# main.net
KiCad netlist of a schematic drawn in Altium Designer
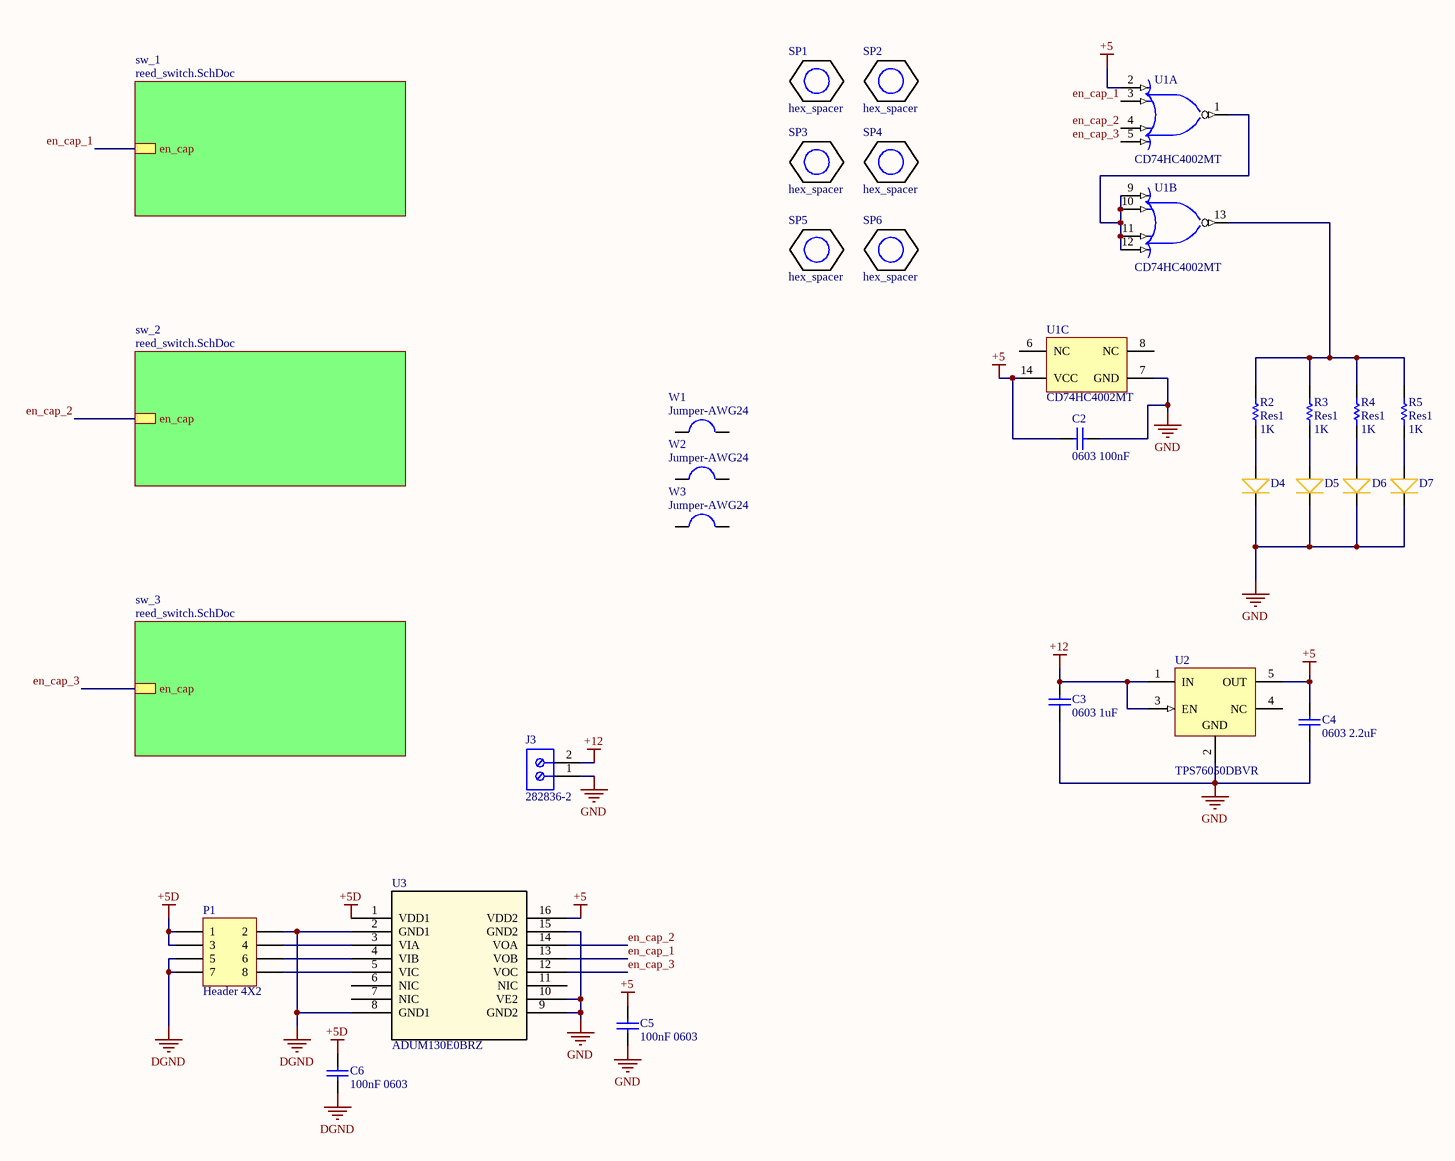
[diagram p0: main.SchDoc]

(export (version "E")
  (design (tool "Eeschema 10.0.6"))
  (components
    (comp (ref "C2")
      (value "0603 100nF")
      (footprint "CAP 0603_1608")
      (description "Capacitor")
      (fields (field (name "PUBLISHER") "Altium Limited"))
      (libsource (lib "Miscellaneous Devices") (part "Cap"))
    )
    (comp (ref "C3")
      (value "0603 1uF")
      (footprint "CAP 0603_1608")
      (description "Capacitor")
      (fields (field (name "PUBLISHER") "Altium Limited"))
      (libsource (lib "Miscellaneous Devices") (part "Cap"))
    )
    (comp (ref "C4")
      (value "0603 2.2uF")
      (footprint "CAP 0603_1608")
      (description "Capacitor")
      (fields (field (name "PUBLISHER") "Altium Limited"))
      (libsource (lib "Miscellaneous Devices") (part "Cap"))
    )
    (comp (ref "C5")
      (value "100nF 0603")
      (footprint "CAP 0603_1608")
      (description "Capacitor")
      (fields (field (name "PUBLISHER") "Altium Limited"))
      (libsource (lib "Miscellaneous Devices") (part "Cap"))
    )
    (comp (ref "C6")
      (value "100nF 0603")
      (footprint "CAP 0603_1608")
      (description "Capacitor")
      (fields (field (name "PUBLISHER") "Altium Limited"))
      (libsource (lib "Miscellaneous Devices") (part "Cap"))
    )
    (comp (ref "D4")
      (value "732-12018-1-ND")
      (footprint "LED_YELLOW_0603")
      (libsource (lib "coil_driver_lib") (part "led_yellow_0603"))
    )
    (comp (ref "D5")
      (value "732-12018-1-ND")
      (footprint "LED_YELLOW_0603")
      (libsource (lib "coil_driver_lib") (part "led_yellow_0603"))
    )
    (comp (ref "D6")
      (value "732-12018-1-ND")
      (footprint "LED_YELLOW_0603")
      (libsource (lib "coil_driver_lib") (part "led_yellow_0603"))
    )
    (comp (ref "D7")
      (value "732-12018-1-ND")
      (footprint "LED_YELLOW_0603")
      (libsource (lib "coil_driver_lib") (part "led_yellow_0603"))
    )
    (comp (ref "J3")
      (value "282836-2")
      (footprint "TECO-282836-2_V")
      (description "Female Header, Pitch 5 mm, 1 x 2 Position, Height 10 mm, Tail Length 3.5 mm, Rohs, Bulk")
      (fields (field (name "VOLTAGE") "300V") (field (name "MANUFACTURER") "TE Connectivity"))
      (libsource (lib "Altium Content Vault") (part "CN-1P-F-TB2"))
    )
    (comp (ref "P1")
      (value "Header 4X2")
      (footprint "HEADER_4_2")
      (description "Header, 4-Pin, Dual row")
      (fields (field (name "PUBLISHER") "Altium Limited"))
      (libsource (lib "Miscellaneous Connectors") (part "Header 4X2"))
    )
    (comp (ref "R2")
      (value "Res1")
      (footprint "RES 0603_1608")
      (description "Resistor")
      (fields (field (name "ALTIUM_VALUE") "1K") (field (name "PUBLISHER") "Altium Limited"))
      (libsource (lib "Miscellaneous Devices") (part "Res1"))
    )
    (comp (ref "R3")
      (value "Res1")
      (footprint "RES 0603_1608")
      (description "Resistor")
      (fields (field (name "ALTIUM_VALUE") "1K") (field (name "PUBLISHER") "Altium Limited"))
      (libsource (lib "Miscellaneous Devices") (part "Res1"))
    )
    (comp (ref "R4")
      (value "Res1")
      (footprint "RES 0603_1608")
      (description "Resistor")
      (fields (field (name "ALTIUM_VALUE") "1K") (field (name "PUBLISHER") "Altium Limited"))
      (libsource (lib "Miscellaneous Devices") (part "Res1"))
    )
    (comp (ref "R5")
      (value "Res1")
      (footprint "RES 0603_1608")
      (description "Resistor")
      (fields (field (name "ALTIUM_VALUE") "1K") (field (name "PUBLISHER") "Altium Limited"))
      (libsource (lib "Miscellaneous Devices") (part "Res1"))
    )
    (comp (ref "SP1")
      (value "hex_spacer")
      (footprint "hex_spacer")
      (libsource (lib "coil_driver_lib") (part "hex_spacer"))
    )
    (comp (ref "SP2")
      (value "hex_spacer")
      (footprint "hex_spacer")
      (libsource (lib "coil_driver_lib") (part "hex_spacer"))
    )
    (comp (ref "SP3")
      (value "hex_spacer")
      (footprint "hex_spacer")
      (libsource (lib "coil_driver_lib") (part "hex_spacer"))
    )
    (comp (ref "SP4")
      (value "hex_spacer")
      (footprint "hex_spacer")
      (libsource (lib "coil_driver_lib") (part "hex_spacer"))
    )
    (comp (ref "SP5")
      (value "hex_spacer")
      (footprint "hex_spacer")
      (libsource (lib "coil_driver_lib") (part "hex_spacer"))
    )
    (comp (ref "SP6")
      (value "hex_spacer")
      (footprint "hex_spacer")
      (libsource (lib "coil_driver_lib") (part "hex_spacer"))
    )
    (comp (ref "U1")
      (value "CD74HC4002MT")
      (footprint "D0014A_N")
      (description "High Speed CMOS Logic Dual 4-Input NOR Gates, D0014A, SMALL T&R")
      (fields
        (field (name "MANUFACTURER") "Texas Instruments")
        (field (name "GENERIC PART NUMBER") "CD74HC4002")
      )
      (libsource (lib "Altium Content Vault") (part "TI-CD_SNX4HC4002-14"))
    )
    (comp (ref "U2")
      (value "TPS76050DBVR")
      (footprint "DBV0005A_L")
      (fields (field (name "MANUFACTURER") "Texas Instruments"))
      (libsource (lib "Altium Content Vault") (part "TI-TXX7XXXX-5"))
    )
    (comp (ref "U3")
      (value "ADUM130E0BRZ")
      (footprint "R_16")
      (description "No Description Available")
      (fields (field (name "COPYRIGHT") "Copyright (C) 2021 Ultra Librarian. All rights reserved."))
      (libsource (lib "ADUM130E0BRZ") (part "ADUM130E0BRZ"))
    )
    (comp (ref "W1")
      (value "wire_jumper")
      (footprint "wire_jumper")
      (libsource (lib "coil_driver_lib") (part "wire_jumper"))
    )
    (comp (ref "W2")
      (value "wire_jumper")
      (footprint "wire_jumper")
      (libsource (lib "coil_driver_lib") (part "wire_jumper"))
    )
    (comp (ref "W3")
      (value "wire_jumper")
      (footprint "wire_jumper")
      (libsource (lib "coil_driver_lib") (part "wire_jumper"))
    )
  )
  (nets
    (net (code "1") (name "+5") (class "Default")
      (node (ref "C2") (pin "2") (pinfunction "2_2") (pintype "passive"))
      (node (ref "C4") (pin "2") (pinfunction "2_2") (pintype "passive"))
      (node (ref "C5") (pin "2") (pinfunction "2_2") (pintype "passive"))
      (node (ref "U1") (pin "14") (pinfunction "VCC_14") (pintype "power_in"))
      (node (ref "U1") (pin "2") (pinfunction "1A_2") (pintype "input"))
      (node (ref "U2") (pin "5") (pinfunction "OUT_5") (pintype "power_in"))
      (node (ref "U3") (pin "16") (pinfunction "VDD2_16") (pintype "passive"))
    )
    (net (code "2") (name "+5D") (class "Default")
      (node (ref "C6") (pin "2") (pinfunction "2_2") (pintype "passive"))
      (node (ref "P1") (pin "1") (pinfunction "1_1") (pintype "passive"))
      (node (ref "P1") (pin "3") (pinfunction "3_3") (pintype "passive"))
      (node (ref "U3") (pin "1") (pinfunction "VDD1_1") (pintype "passive"))
    )
    (net (code "3") (name "+12") (class "Default")
      (node (ref "C3") (pin "2") (pinfunction "2_2") (pintype "passive"))
      (node (ref "J3") (pin "2") (pinfunction "2_2") (pintype "passive"))
      (node (ref "U2") (pin "1") (pinfunction "IN_1") (pintype "power_in"))
      (node (ref "U2") (pin "3") (pinfunction "EN_3") (pintype "input"))
    )
    (net (code "4") (name "/en_cap_1") (class "Default")
      (node (ref "U1") (pin "3") (pinfunction "1B_3") (pintype "input"))
      (node (ref "U3") (pin "13") (pinfunction "VOB_13") (pintype "passive"))
    )
    (net (code "5") (name "/en_cap_2") (class "Default")
      (node (ref "U1") (pin "4") (pinfunction "1C_4") (pintype "input"))
      (node (ref "U3") (pin "14") (pinfunction "VOA_14") (pintype "passive"))
    )
    (net (code "6") (name "/en_cap_3") (class "Default")
      (node (ref "U1") (pin "5") (pinfunction "1D_5") (pintype "input"))
      (node (ref "U3") (pin "12") (pinfunction "VOC_12") (pintype "passive"))
    )
    (net (code "7") (name "DGND") (class "Default")
      (node (ref "C6") (pin "1") (pinfunction "1_1") (pintype "passive"))
      (node (ref "P1") (pin "2") (pinfunction "2_2") (pintype "passive"))
      (node (ref "P1") (pin "5") (pinfunction "5_5") (pintype "passive"))
      (node (ref "P1") (pin "7") (pinfunction "7_7") (pintype "passive"))
      (node (ref "U3") (pin "2") (pinfunction "GND1_2") (pintype "passive"))
      (node (ref "U3") (pin "8") (pinfunction "GND1_8") (pintype "passive"))
    )
    (net (code "8") (name "GND") (class "Default")
      (node (ref "C2") (pin "1") (pinfunction "1_1") (pintype "passive"))
      (node (ref "C3") (pin "1") (pinfunction "1_1") (pintype "passive"))
      (node (ref "C4") (pin "1") (pinfunction "1_1") (pintype "passive"))
      (node (ref "C5") (pin "1") (pinfunction "1_1") (pintype "passive"))
      (node (ref "D4") (pin "C") (pinfunction "C_C") (pintype "passive"))
      (node (ref "D5") (pin "C") (pinfunction "C_C") (pintype "passive"))
      (node (ref "D6") (pin "C") (pinfunction "C_C") (pintype "passive"))
      (node (ref "D7") (pin "C") (pinfunction "C_C") (pintype "passive"))
      (node (ref "J3") (pin "1") (pinfunction "1_1") (pintype "passive"))
      (node (ref "U1") (pin "7") (pinfunction "GND_7") (pintype "power_in"))
      (node (ref "U2") (pin "2") (pinfunction "GND_2") (pintype "power_in"))
      (node (ref "U3") (pin "10") (pinfunction "VE2_10") (pintype "passive"))
      (node (ref "U3") (pin "15") (pinfunction "GND2_15") (pintype "passive"))
      (node (ref "U3") (pin "9") (pinfunction "GND2_9") (pintype "passive"))
    )
    (net (code "9") (name "Net-(D4-PadA)") (class "Default")
      (node (ref "D4") (pin "A") (pinfunction "A_A") (pintype "passive"))
      (node (ref "R2") (pin "1") (pinfunction "1_1") (pintype "passive"))
    )
    (net (code "10") (name "Net-(D5-PadA)") (class "Default")
      (node (ref "D5") (pin "A") (pinfunction "A_A") (pintype "passive"))
      (node (ref "R3") (pin "1") (pinfunction "1_1") (pintype "passive"))
    )
    (net (code "11") (name "Net-(D6-PadA)") (class "Default")
      (node (ref "D6") (pin "A") (pinfunction "A_A") (pintype "passive"))
      (node (ref "R4") (pin "1") (pinfunction "1_1") (pintype "passive"))
    )
    (net (code "12") (name "Net-(D7-PadA)") (class "Default")
      (node (ref "D7") (pin "A") (pinfunction "A_A") (pintype "passive"))
      (node (ref "R5") (pin "1") (pinfunction "1_1") (pintype "passive"))
    )
    (net (code "13") (name "Net-(U1A-1Y)") (class "Default")
      (node (ref "U1") (pin "1") (pinfunction "1Y_1") (pintype "output"))
      (node (ref "U1") (pin "10") (pinfunction "2B_10") (pintype "input"))
      (node (ref "U1") (pin "11") (pinfunction "2C_11") (pintype "input"))
      (node (ref "U1") (pin "12") (pinfunction "2D_12") (pintype "input"))
      (node (ref "U1") (pin "9") (pinfunction "2A_9") (pintype "input"))
    )
    (net (code "14") (name "Net-(U1B-2Y)") (class "Default")
      (node (ref "R2") (pin "2") (pinfunction "2_2") (pintype "passive"))
      (node (ref "R3") (pin "2") (pinfunction "2_2") (pintype "passive"))
      (node (ref "R4") (pin "2") (pinfunction "2_2") (pintype "passive"))
      (node (ref "R5") (pin "2") (pinfunction "2_2") (pintype "passive"))
      (node (ref "U1") (pin "13") (pinfunction "2Y_13") (pintype "output"))
    )
    (net (code "15") (name "Net-(U3-VIA)") (class "Default")
      (node (ref "P1") (pin "4") (pinfunction "4_4") (pintype "passive"))
      (node (ref "U3") (pin "3") (pinfunction "VIA_3") (pintype "passive"))
    )
    (net (code "16") (name "Net-(U3-VIB)") (class "Default")
      (node (ref "P1") (pin "6") (pinfunction "6_6") (pintype "passive"))
      (node (ref "U3") (pin "4") (pinfunction "VIB_4") (pintype "passive"))
    )
    (net (code "17") (name "Net-(U3-VIC)") (class "Default")
      (node (ref "P1") (pin "8") (pinfunction "8_8") (pintype "passive"))
      (node (ref "U3") (pin "5") (pinfunction "VIC_5") (pintype "passive"))
    )
    (net (code "18") (name "unconnected-(U1C-NC-Pad6)") (class "Default")
      (node (ref "U1") (pin "6") (pinfunction "NC_6") (pintype "passive"))
    )
    (net (code "19") (name "unconnected-(U1C-NC-Pad8)") (class "Default")
      (node (ref "U1") (pin "8") (pinfunction "NC_8") (pintype "passive"))
    )
    (net (code "20") (name "unconnected-(U2-NC-Pad4)") (class "Default")
      (node (ref "U2") (pin "4") (pinfunction "NC_4") (pintype "passive"))
    )
    (net (code "21") (name "unconnected-(U3-NIC-Pad6)") (class "Default")
      (node (ref "U3") (pin "6") (pinfunction "NIC_6") (pintype "passive"))
    )
    (net (code "22") (name "unconnected-(U3-NIC-Pad7)") (class "Default")
      (node (ref "U3") (pin "7") (pinfunction "NIC_7") (pintype "passive"))
    )
    (net (code "23") (name "unconnected-(U3-NIC-Pad11)") (class "Default")
      (node (ref "U3") (pin "11") (pinfunction "NIC_11") (pintype "passive"))
    )
    (net (code "24") (name "unconnected-(W1-Pad1)") (class "Default")
      (node (ref "W1") (pin "1") (pinfunction "1_1") (pintype "passive"))
    )
    (net (code "25") (name "unconnected-(W1-Pad2)") (class "Default")
      (node (ref "W1") (pin "2") (pinfunction "2_2") (pintype "passive"))
    )
    (net (code "26") (name "unconnected-(W2-Pad1)") (class "Default")
      (node (ref "W2") (pin "1") (pinfunction "1_1") (pintype "passive"))
    )
    (net (code "27") (name "unconnected-(W2-Pad2)") (class "Default")
      (node (ref "W2") (pin "2") (pinfunction "2_2") (pintype "passive"))
    )
    (net (code "28") (name "unconnected-(W3-Pad1)") (class "Default")
      (node (ref "W3") (pin "1") (pinfunction "1_1") (pintype "passive"))
    )
    (net (code "29") (name "unconnected-(W3-Pad2)") (class "Default")
      (node (ref "W3") (pin "2") (pinfunction "2_2") (pintype "passive"))
    )
  )
)
